# 1_AT_Link_ISO_Interface.net
KiCad netlist of a schematic drawn in Altium Designer
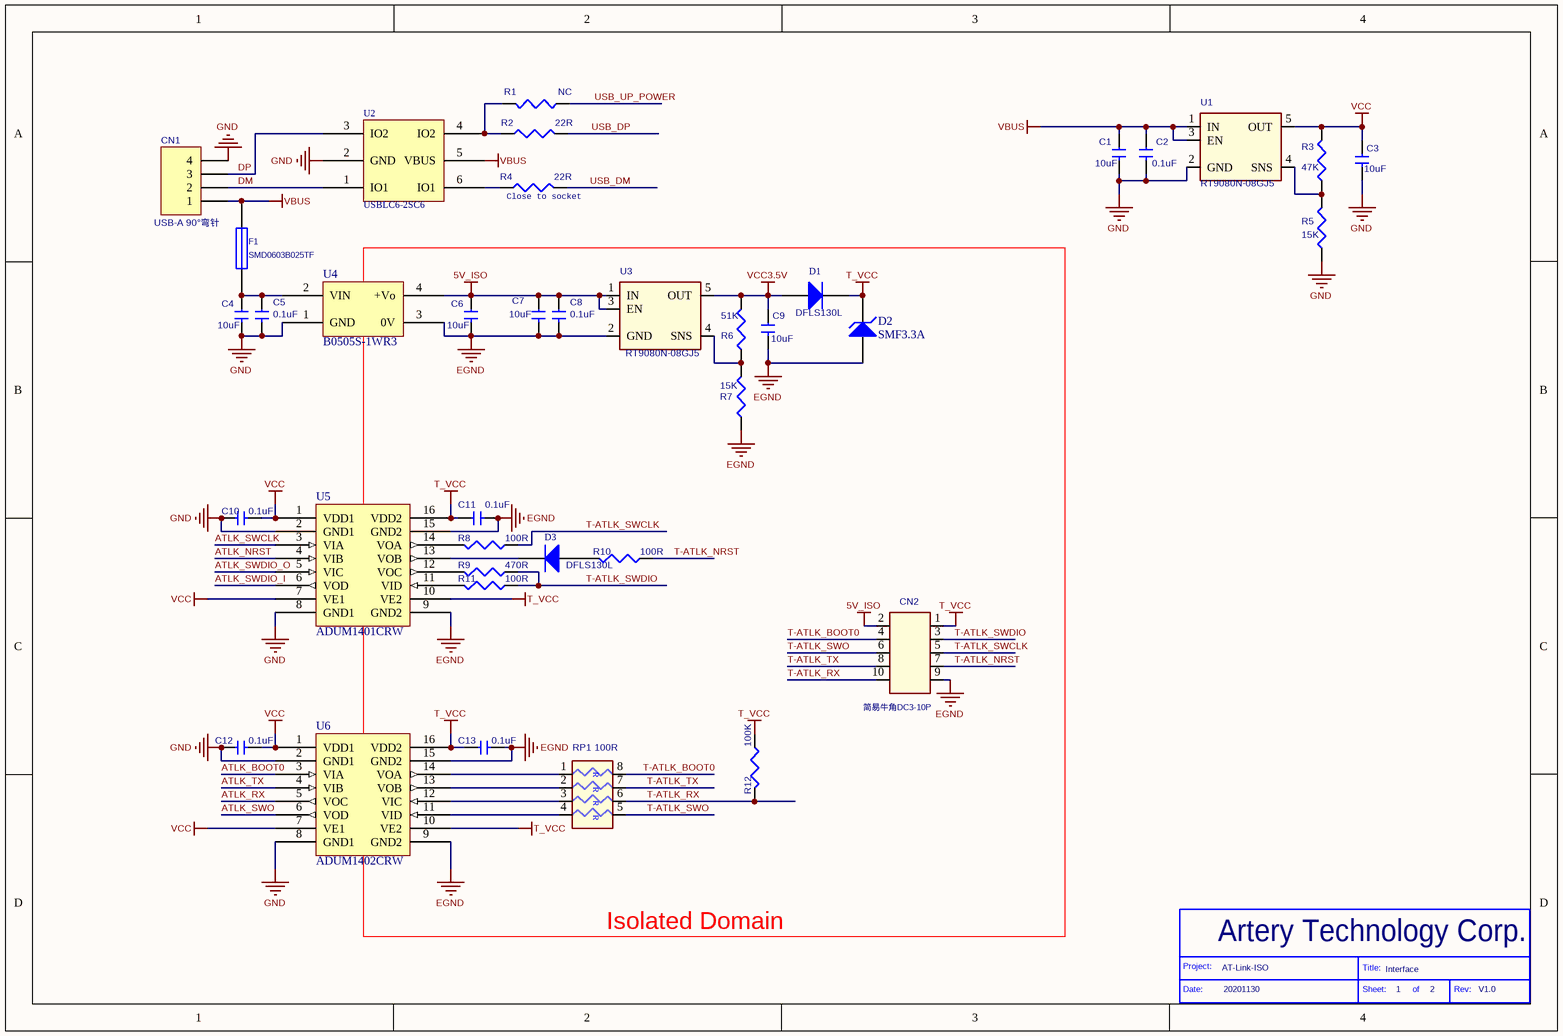
[diagram p0: 1_AT_Link_ISO_Interface.SchDoc]

(export (version "E")
  (design (tool "Eeschema 10.0.6"))
  (components
    (comp (ref "C1")
      (value "10uF")
      (description "贴片陶瓷电容 10uF,16V,10%,X7R,SMD0603")
      (libsource (lib "*") (part "0.1uF,50V,20%,SMD0603"))
    )
    (comp (ref "C2")
      (value "0.1uF")
      (description "贴片陶瓷电容 0.1uF,16V,10%,X7R,SMD0603")
      (libsource (lib "*") (part "0.1uF,50V,20%,SMD0603"))
    )
    (comp (ref "C3")
      (value "10uF")
      (description "贴片陶瓷电容 10uF,16V,10%,X7R,SMD0603")
      (libsource (lib "*") (part "0.1uF,50V,20%,SMD0603"))
    )
    (comp (ref "C4")
      (value "10uF")
      (description "贴片陶瓷电容 10uF,16V,10%,X7R,SMD0603")
      (libsource (lib "*") (part "0.1uF,50V,20%,SMD0603"))
    )
    (comp (ref "C5")
      (value "0.1uF")
      (description "贴片陶瓷电容 0.1uF,16V,10%,X7R,SMD0603")
      (libsource (lib "*") (part "0.1uF,50V,20%,SMD0603"))
    )
    (comp (ref "C6")
      (value "10uF")
      (description "贴片陶瓷电容 10uF,16V,10%,X7R,SMD0603")
      (libsource (lib "*") (part "0.1uF,50V,20%,SMD0603"))
    )
    (comp (ref "C7")
      (value "10uF")
      (description "贴片陶瓷电容 10uF,16V,10%,X7R,SMD0603")
      (libsource (lib "*") (part "0.1uF,50V,20%,SMD0603"))
    )
    (comp (ref "C8")
      (value "0.1uF")
      (description "贴片陶瓷电容 0.1uF,16V,10%,X7R,SMD0603")
      (libsource (lib "*") (part "0.1uF,50V,20%,SMD0603"))
    )
    (comp (ref "C9")
      (value "10uF")
      (description "贴片陶瓷电容 10uF,16V,10%,X7R,SMD0603")
      (libsource (lib "*") (part "0.1uF,50V,20%,SMD0603"))
    )
    (comp (ref "C10")
      (value "0.1uF")
      (description "贴片陶瓷电容 0.1uF,16V,10%,X7R,SMD0603")
      (libsource (lib "*") (part "0.1uF,50V,20%,SMD0603"))
    )
    (comp (ref "C11")
      (value "0.1uF")
      (description "贴片陶瓷电容 0.1uF,16V,10%,X7R,SMD0603")
      (libsource (lib "*") (part "0.1uF,50V,20%,SMD0603"))
    )
    (comp (ref "C12")
      (value "0.1uF")
      (description "贴片陶瓷电容 0.1uF,16V,10%,X7R,SMD0603")
      (libsource (lib "*") (part "0.1uF,50V,20%,SMD0603"))
    )
    (comp (ref "C13")
      (value "0.1uF")
      (description "贴片陶瓷电容 0.1uF,16V,10%,X7R,SMD0603")
      (libsource (lib "*") (part "0.1uF,50V,20%,SMD0603"))
    )
    (comp (ref "CN1")
      (value "USB-A 90°弯针")
      (footprint "USB_A - Dip")
      (description "USB-A公头 /90°脚/直插式")
      (fields (field (name "PUBLISHER") "Altium Limited"))
      (libsource (lib "Miscellaneous Connectors") (part "Header 4"))
    )
    (comp (ref "CN2")
      (value "CON1")
      (footprint "SWD_2*5P_SMT")
      (description "简易牛角DC3-10P 直针 2.54mm 2*5P双排 黑色")
      (libsource (lib "*") (part "CON10A_0"))
    )
    (comp (ref "D1")
      (value "DFLS130L")
      (footprint "SOD-123")
      (description "贴片二极管 DFLS130L-7")
      (fields (field (name "PUBLISHER") "Altium Limited"))
      (libsource (lib "Miscellaneous Devices") (part "Diode"))
    )
    (comp (ref "D2")
      (value "SMF3.3A")
      (footprint "SOD-123")
      (description "TVS管SMF3.3A")
      (libsource (lib "Artery_PCB_LIB") (part "SMF3.3A"))
    )
    (comp (ref "D3")
      (value "DFLS130L")
      (footprint "SOD-123")
      (description "贴片二极管 DFLS130L-7")
      (fields (field (name "PUBLISHER") "Altium Limited"))
      (libsource (lib "Miscellaneous Devices") (part "Diode"))
    )
    (comp (ref "F1")
      (value "SMD0603B025TF")
      (footprint "0603_r")
      (description "SMD0603B025TF 可恢复保险丝")
      (fields (field (name "PUBLISHER") "Altium Limited"))
      (libsource (lib "Miscellaneous Devices") (part "Fuse 1"))
    )
    (comp (ref "R1") (value "NC") (libsource (lib "*") (part "10K,1/10W,1%,SMD0603_Dup1")))
    (comp (ref "R2")
      (value "22R")
      (description "贴片电阻 22R 5% 1/10W 0603")
      (libsource (lib "*") (part "22,1/10W,1%,SMD0603"))
    )
    (comp (ref "R3")
      (value "47K")
      (description "贴片电阻 47K 1% 1/10W 0603")
      (libsource (lib "*") (part "470,1/10W,1%,SMD0603"))
    )
    (comp (ref "R4")
      (value "22R")
      (description "贴片电阻 22R 5% 1/10W 0603")
      (libsource (lib "*") (part "22,1/10W,1%,SMD0603"))
    )
    (comp (ref "R5")
      (value "15K")
      (description "贴片电阻 15K 1% 1/10W 0603")
      (libsource (lib "*") (part "470,1/10W,1%,SMD0603"))
    )
    (comp (ref "R6")
      (value "51K")
      (description "贴片电阻 51K 1% 1/10W 0603")
      (libsource (lib "*") (part "470,1/10W,1%,SMD0603"))
    )
    (comp (ref "R7")
      (value "15K")
      (description "贴片电阻 15K 1% 1/10W 0603")
      (libsource (lib "*") (part "470,1/10W,1%,SMD0603"))
    )
    (comp (ref "R8")
      (value "100R")
      (description "贴片电阻 100R 5% 1/10W 0603")
      (libsource (lib "*") (part "22,1/10W,1%,SMD0603"))
    )
    (comp (ref "R9")
      (value "470R")
      (description "贴片电阻 470R 5% 1/10W 0603")
      (libsource (lib "*") (part "22,1/10W,1%,SMD0603"))
    )
    (comp (ref "R10")
      (value "100R")
      (description "贴片电阻 100R 5% 1/10W 0603")
      (libsource (lib "*") (part "22,1/10W,1%,SMD0603"))
    )
    (comp (ref "R11")
      (value "100R")
      (description "贴片电阻 100R 5% 1/10W 0603")
      (libsource (lib "*") (part "22,1/10W,1%,SMD0603"))
    )
    (comp (ref "R12")
      (value "100K")
      (description "贴片电阻 100K 5% 1/10W 0603")
      (libsource (lib "*") (part "22,1/10W,1%,SMD0603"))
    )
    (comp (ref "RP1")
      (value "100R")
      (description "贴片排阻 100R 5% 1/16W 0603")
      (libsource (lib "*") (part "22,1/16W,5%,8P4R"))
    )
    (comp (ref "U1") (value "RT9080N-08GJ5") (libsource (lib "SCM_START_402F") (part "RT9080N")))
    (comp (ref "U2")
      (value "USBLC6-2SC6")
      (footprint "SOT-23-6")
      (libsource (lib "Schlib1") (part "USBLC6-2SC6"))
    )
    (comp (ref "U3") (value "RT9080N-08GJ5") (libsource (lib "SCM_START_402F") (part "RT9080N")))
    (comp (ref "U4")
      (value "B0505S-1WR3")
      (footprint "B0505S-1WR3-B")
      (libsource (lib "Device") (part "B0505S-1WR3"))
    )
    (comp (ref "U5")
      (value "ADUM1401CRW")
      (footprint "SOIC-16_300mil")
      (libsource (lib "Device") (part "ADUM1401CRW"))
    )
    (comp (ref "U6")
      (value "ADUM1402CRW")
      (footprint "SOIC-16_300mil")
      (libsource (lib "Device") (part "ADUM1402CRW"))
    )
  )
  (nets
    (net (code "1") (name "/ATLK_BOOT0") (class "Default")
      (node (ref "U6") (pin "3") (pinfunction "VIA_3") (pintype "input"))
    )
    (net (code "2") (name "/ATLK_NRST") (class "Default")
      (node (ref "U5") (pin "4") (pinfunction "VIB_4") (pintype "input"))
    )
    (net (code "3") (name "/ATLK_RX") (class "Default")
      (node (ref "U6") (pin "5") (pinfunction "VOC_5") (pintype "output"))
    )
    (net (code "4") (name "/ATLK_SWCLK") (class "Default")
      (node (ref "U5") (pin "3") (pinfunction "VIA_3") (pintype "input"))
    )
    (net (code "5") (name "/ATLK_SWDIO_I") (class "Default")
      (node (ref "U5") (pin "6") (pinfunction "VOD_6") (pintype "output"))
    )
    (net (code "6") (name "/ATLK_SWDIO_O") (class "Default")
      (node (ref "U5") (pin "5") (pinfunction "VIC_5") (pintype "input"))
    )
    (net (code "7") (name "/ATLK_SWO") (class "Default")
      (node (ref "U6") (pin "6") (pinfunction "VOD_6") (pintype "output"))
    )
    (net (code "8") (name "/ATLK_TX") (class "Default")
      (node (ref "U6") (pin "4") (pinfunction "VIB_4") (pintype "input"))
    )
    (net (code "9") (name "/DM") (class "Default")
      (node (ref "CN1") (pin "2") (pinfunction "2_2") (pintype "passive"))
      (node (ref "U2") (pin "1") (pinfunction "IO1_1") (pintype "passive"))
    )
    (net (code "10") (name "/DP") (class "Default")
      (node (ref "CN1") (pin "3") (pinfunction "3_3") (pintype "passive"))
      (node (ref "U2") (pin "3") (pinfunction "IO2_3") (pintype "passive"))
    )
    (net (code "11") (name "/T-ATLK_BOOT0") (class "Default")
      (node (ref "CN2") (pin "4") (pinfunction "4_4") (pintype "passive"))
      (node (ref "RP1") (pin "8") (pinfunction "8_8") (pintype "passive"))
    )
    (net (code "12") (name "/T-ATLK_NRST") (class "Default")
      (node (ref "CN2") (pin "7") (pinfunction "7_7") (pintype "passive"))
      (node (ref "R10") (pin "1") (pinfunction "1_1") (pintype "passive"))
    )
    (net (code "13") (name "/T-ATLK_RX") (class "Default")
      (node (ref "CN2") (pin "10") (pinfunction "10_10") (pintype "passive"))
      (node (ref "R12") (pin "2") (pinfunction "2_2") (pintype "passive"))
      (node (ref "RP1") (pin "6") (pinfunction "6_6") (pintype "passive"))
    )
    (net (code "14") (name "/T-ATLK_SWCLK") (class "Default")
      (node (ref "CN2") (pin "5") (pinfunction "5_5") (pintype "passive"))
      (node (ref "R8") (pin "1") (pinfunction "1_1") (pintype "passive"))
    )
    (net (code "15") (name "/T-ATLK_SWDIO") (class "Default")
      (node (ref "CN2") (pin "3") (pinfunction "3_3") (pintype "passive"))
      (node (ref "R11") (pin "1") (pinfunction "1_1") (pintype "passive"))
      (node (ref "R9") (pin "1") (pinfunction "1_1") (pintype "passive"))
    )
    (net (code "16") (name "/T-ATLK_SWO") (class "Default")
      (node (ref "CN2") (pin "6") (pinfunction "6_6") (pintype "passive"))
      (node (ref "RP1") (pin "5") (pinfunction "5_5") (pintype "passive"))
    )
    (net (code "17") (name "/T-ATLK_TX") (class "Default")
      (node (ref "CN2") (pin "8") (pinfunction "8_8") (pintype "passive"))
      (node (ref "RP1") (pin "7") (pinfunction "7_7") (pintype "passive"))
    )
    (net (code "18") (name "/USB_DM") (class "Default")
      (node (ref "R4") (pin "2") (pinfunction "2_2") (pintype "passive"))
    )
    (net (code "19") (name "/USB_DP") (class "Default")
      (node (ref "R2") (pin "2") (pinfunction "2_2") (pintype "passive"))
    )
    (net (code "20") (name "/USB_UP_POWER") (class "Default")
      (node (ref "R1") (pin "1") (pinfunction "1_1") (pintype "passive"))
    )
    (net (code "21") (name "5V_ISO") (class "Default")
      (node (ref "C6") (pin "1") (pinfunction "1_1") (pintype "passive"))
      (node (ref "C7") (pin "1") (pinfunction "1_1") (pintype "passive"))
      (node (ref "C8") (pin "1") (pinfunction "1_1") (pintype "passive"))
      (node (ref "CN2") (pin "2") (pinfunction "2_2") (pintype "passive"))
      (node (ref "U3") (pin "1") (pinfunction "IN_1") (pintype "power_in"))
      (node (ref "U3") (pin "3") (pinfunction "EN_3") (pintype "passive"))
      (node (ref "U4") (pin "4") (pinfunction "+Vo_4") (pintype "power_in"))
    )
    (net (code "22") (name "EGND") (class "Default")
      (node (ref "C11") (pin "2") (pinfunction "2_2") (pintype "passive"))
      (node (ref "C13") (pin "2") (pinfunction "2_2") (pintype "passive"))
      (node (ref "C6") (pin "2") (pinfunction "2_2") (pintype "passive"))
      (node (ref "C7") (pin "2") (pinfunction "2_2") (pintype "passive"))
      (node (ref "C8") (pin "2") (pinfunction "2_2") (pintype "passive"))
      (node (ref "C9") (pin "2") (pinfunction "2_2") (pintype "passive"))
      (node (ref "CN2") (pin "9") (pinfunction "9_9") (pintype "passive"))
      (node (ref "D2") (pin "1") (pinfunction "A_1") (pintype "passive"))
      (node (ref "R7") (pin "1") (pinfunction "1_1") (pintype "passive"))
      (node (ref "U3") (pin "2") (pinfunction "GND_2") (pintype "power_in"))
      (node (ref "U4") (pin "3") (pinfunction "0V_3") (pintype "power_in"))
      (node (ref "U5") (pin "15") (pinfunction "GND2_15") (pintype "power_in"))
      (node (ref "U5") (pin "9") (pinfunction "GND2_9") (pintype "power_in"))
      (node (ref "U6") (pin "15") (pinfunction "GND2_15") (pintype "power_in"))
      (node (ref "U6") (pin "9") (pinfunction "GND2_9") (pintype "power_in"))
    )
    (net (code "23") (name "GND") (class "Default")
      (node (ref "C1") (pin "2") (pinfunction "2_2") (pintype "passive"))
      (node (ref "C10") (pin "1") (pinfunction "1_1") (pintype "passive"))
      (node (ref "C12") (pin "1") (pinfunction "1_1") (pintype "passive"))
      (node (ref "C2") (pin "2") (pinfunction "2_2") (pintype "passive"))
      (node (ref "C3") (pin "2") (pinfunction "2_2") (pintype "passive"))
      (node (ref "C4") (pin "2") (pinfunction "2_2") (pintype "passive"))
      (node (ref "C5") (pin "2") (pinfunction "2_2") (pintype "passive"))
      (node (ref "CN1") (pin "4") (pinfunction "4_4") (pintype "passive"))
      (node (ref "R5") (pin "1") (pinfunction "1_1") (pintype "passive"))
      (node (ref "U1") (pin "2") (pinfunction "GND_2") (pintype "power_in"))
      (node (ref "U2") (pin "2") (pinfunction "GND_2") (pintype "passive"))
      (node (ref "U4") (pin "1") (pinfunction "GND_1") (pintype "power_in"))
      (node (ref "U5") (pin "2") (pinfunction "GND1_2") (pintype "power_in"))
      (node (ref "U5") (pin "8") (pinfunction "GND1_8") (pintype "power_in"))
      (node (ref "U6") (pin "2") (pinfunction "GND1_2") (pintype "power_in"))
      (node (ref "U6") (pin "8") (pinfunction "GND1_8") (pintype "power_in"))
    )
    (net (code "24") (name "Net-(D3-A)") (class "Default")
      (node (ref "D3") (pin "1") (pinfunction "A_1") (pintype "passive"))
      (node (ref "R10") (pin "2") (pinfunction "2_2") (pintype "passive"))
    )
    (net (code "25") (name "Net-(D3-K)") (class "Default")
      (node (ref "D3") (pin "2") (pinfunction "K_2") (pintype "passive"))
      (node (ref "U5") (pin "13") (pinfunction "VOB_13") (pintype "output"))
    )
    (net (code "26") (name "Net-(R1-Pad2)") (class "Default")
      (node (ref "R1") (pin "2") (pinfunction "2_2") (pintype "passive"))
      (node (ref "R2") (pin "1") (pinfunction "1_1") (pintype "passive"))
      (node (ref "U2") (pin "4") (pinfunction "IO2_4") (pintype "passive"))
    )
    (net (code "27") (name "Net-(R4-Pad1)") (class "Default")
      (node (ref "R4") (pin "1") (pinfunction "1_1") (pintype "passive"))
      (node (ref "U2") (pin "6") (pinfunction "IO1_6") (pintype "passive"))
    )
    (net (code "28") (name "Net-(U1-SNS)") (class "Default")
      (node (ref "R3") (pin "1") (pinfunction "1_1") (pintype "passive"))
      (node (ref "R5") (pin "2") (pinfunction "2_2") (pintype "passive"))
      (node (ref "U1") (pin "4") (pinfunction "SNS_4") (pintype "passive"))
    )
    (net (code "29") (name "Net-(U3-SNS)") (class "Default")
      (node (ref "R6") (pin "1") (pinfunction "1_1") (pintype "passive"))
      (node (ref "R7") (pin "2") (pinfunction "2_2") (pintype "passive"))
      (node (ref "U3") (pin "4") (pinfunction "SNS_4") (pintype "passive"))
    )
    (net (code "30") (name "Net-(U4-VIN)") (class "Default")
      (node (ref "C4") (pin "1") (pinfunction "1_1") (pintype "passive"))
      (node (ref "C5") (pin "1") (pinfunction "1_1") (pintype "passive"))
      (node (ref "F1") (pin "1") (pinfunction "1_1") (pintype "passive"))
      (node (ref "U4") (pin "2") (pinfunction "VIN_2") (pintype "power_in"))
    )
    (net (code "31") (name "Net-(U5-VID)") (class "Default")
      (node (ref "R11") (pin "2") (pinfunction "2_2") (pintype "passive"))
      (node (ref "U5") (pin "11") (pinfunction "VID_11") (pintype "input"))
    )
    (net (code "32") (name "Net-(U5-VOA)") (class "Default")
      (node (ref "R8") (pin "2") (pinfunction "2_2") (pintype "passive"))
      (node (ref "U5") (pin "14") (pinfunction "VOA_14") (pintype "output"))
    )
    (net (code "33") (name "Net-(U5-VOC)") (class "Default")
      (node (ref "R9") (pin "2") (pinfunction "2_2") (pintype "passive"))
      (node (ref "U5") (pin "12") (pinfunction "VOC_12") (pintype "output"))
    )
    (net (code "34") (name "Net-(U6-VIC)") (class "Default")
      (node (ref "RP1") (pin "3") (pinfunction "3_3") (pintype "passive"))
      (node (ref "U6") (pin "12") (pinfunction "VIC_12") (pintype "input"))
    )
    (net (code "35") (name "Net-(U6-VID)") (class "Default")
      (node (ref "RP1") (pin "4") (pinfunction "4_4") (pintype "passive"))
      (node (ref "U6") (pin "11") (pinfunction "VID_11") (pintype "input"))
    )
    (net (code "36") (name "Net-(U6-VOA)") (class "Default")
      (node (ref "RP1") (pin "1") (pinfunction "1_1") (pintype "passive"))
      (node (ref "U6") (pin "14") (pinfunction "VOA_14") (pintype "output"))
    )
    (net (code "37") (name "Net-(U6-VOB)") (class "Default")
      (node (ref "RP1") (pin "2") (pinfunction "2_2") (pintype "passive"))
      (node (ref "U6") (pin "13") (pinfunction "VOB_13") (pintype "output"))
    )
    (net (code "38") (name "T_VCC") (class "Default")
      (node (ref "C11") (pin "1") (pinfunction "1_1") (pintype "passive"))
      (node (ref "C13") (pin "1") (pinfunction "1_1") (pintype "passive"))
      (node (ref "CN2") (pin "1") (pinfunction "1_1") (pintype "passive"))
      (node (ref "D1") (pin "2") (pinfunction "K_2") (pintype "passive"))
      (node (ref "D2") (pin "2") (pinfunction "K_2") (pintype "passive"))
      (node (ref "R12") (pin "1") (pinfunction "1_1") (pintype "passive"))
      (node (ref "U5") (pin "10") (pinfunction "VE2_10") (pintype "passive"))
      (node (ref "U5") (pin "16") (pinfunction "VDD2_16") (pintype "power_in"))
      (node (ref "U6") (pin "10") (pinfunction "VE2_10") (pintype "passive"))
      (node (ref "U6") (pin "16") (pinfunction "VDD2_16") (pintype "power_in"))
    )
    (net (code "39") (name "VBUS") (class "Default")
      (node (ref "C1") (pin "1") (pinfunction "1_1") (pintype "passive"))
      (node (ref "C2") (pin "1") (pinfunction "1_1") (pintype "passive"))
      (node (ref "CN1") (pin "1") (pinfunction "1_1") (pintype "passive"))
      (node (ref "F1") (pin "2") (pinfunction "2_2") (pintype "passive"))
      (node (ref "U1") (pin "1") (pinfunction "IN_1") (pintype "power_in"))
      (node (ref "U1") (pin "3") (pinfunction "EN_3") (pintype "passive"))
      (node (ref "U2") (pin "5") (pinfunction "VBUS_5") (pintype "passive"))
    )
    (net (code "40") (name "VCC") (class "Default")
      (node (ref "C10") (pin "2") (pinfunction "2_2") (pintype "passive"))
      (node (ref "C12") (pin "2") (pinfunction "2_2") (pintype "passive"))
      (node (ref "C3") (pin "1") (pinfunction "1_1") (pintype "passive"))
      (node (ref "R3") (pin "2") (pinfunction "2_2") (pintype "passive"))
      (node (ref "U1") (pin "5") (pinfunction "OUT_5") (pintype "power_in"))
      (node (ref "U5") (pin "1") (pinfunction "VDD1_1") (pintype "power_in"))
      (node (ref "U5") (pin "7") (pinfunction "VE1_7") (pintype "passive"))
      (node (ref "U6") (pin "1") (pinfunction "VDD1_1") (pintype "power_in"))
      (node (ref "U6") (pin "7") (pinfunction "VE1_7") (pintype "passive"))
    )
    (net (code "41") (name "VCC3.5V") (class "Default")
      (node (ref "C9") (pin "1") (pinfunction "1_1") (pintype "passive"))
      (node (ref "D1") (pin "1") (pinfunction "A_1") (pintype "passive"))
      (node (ref "R6") (pin "2") (pinfunction "2_2") (pintype "passive"))
      (node (ref "U3") (pin "5") (pinfunction "OUT_5") (pintype "power_in"))
    )
  )
)
